# Metlino_MCH.net
KiCad netlist of a schematic drawn in Altium Designer
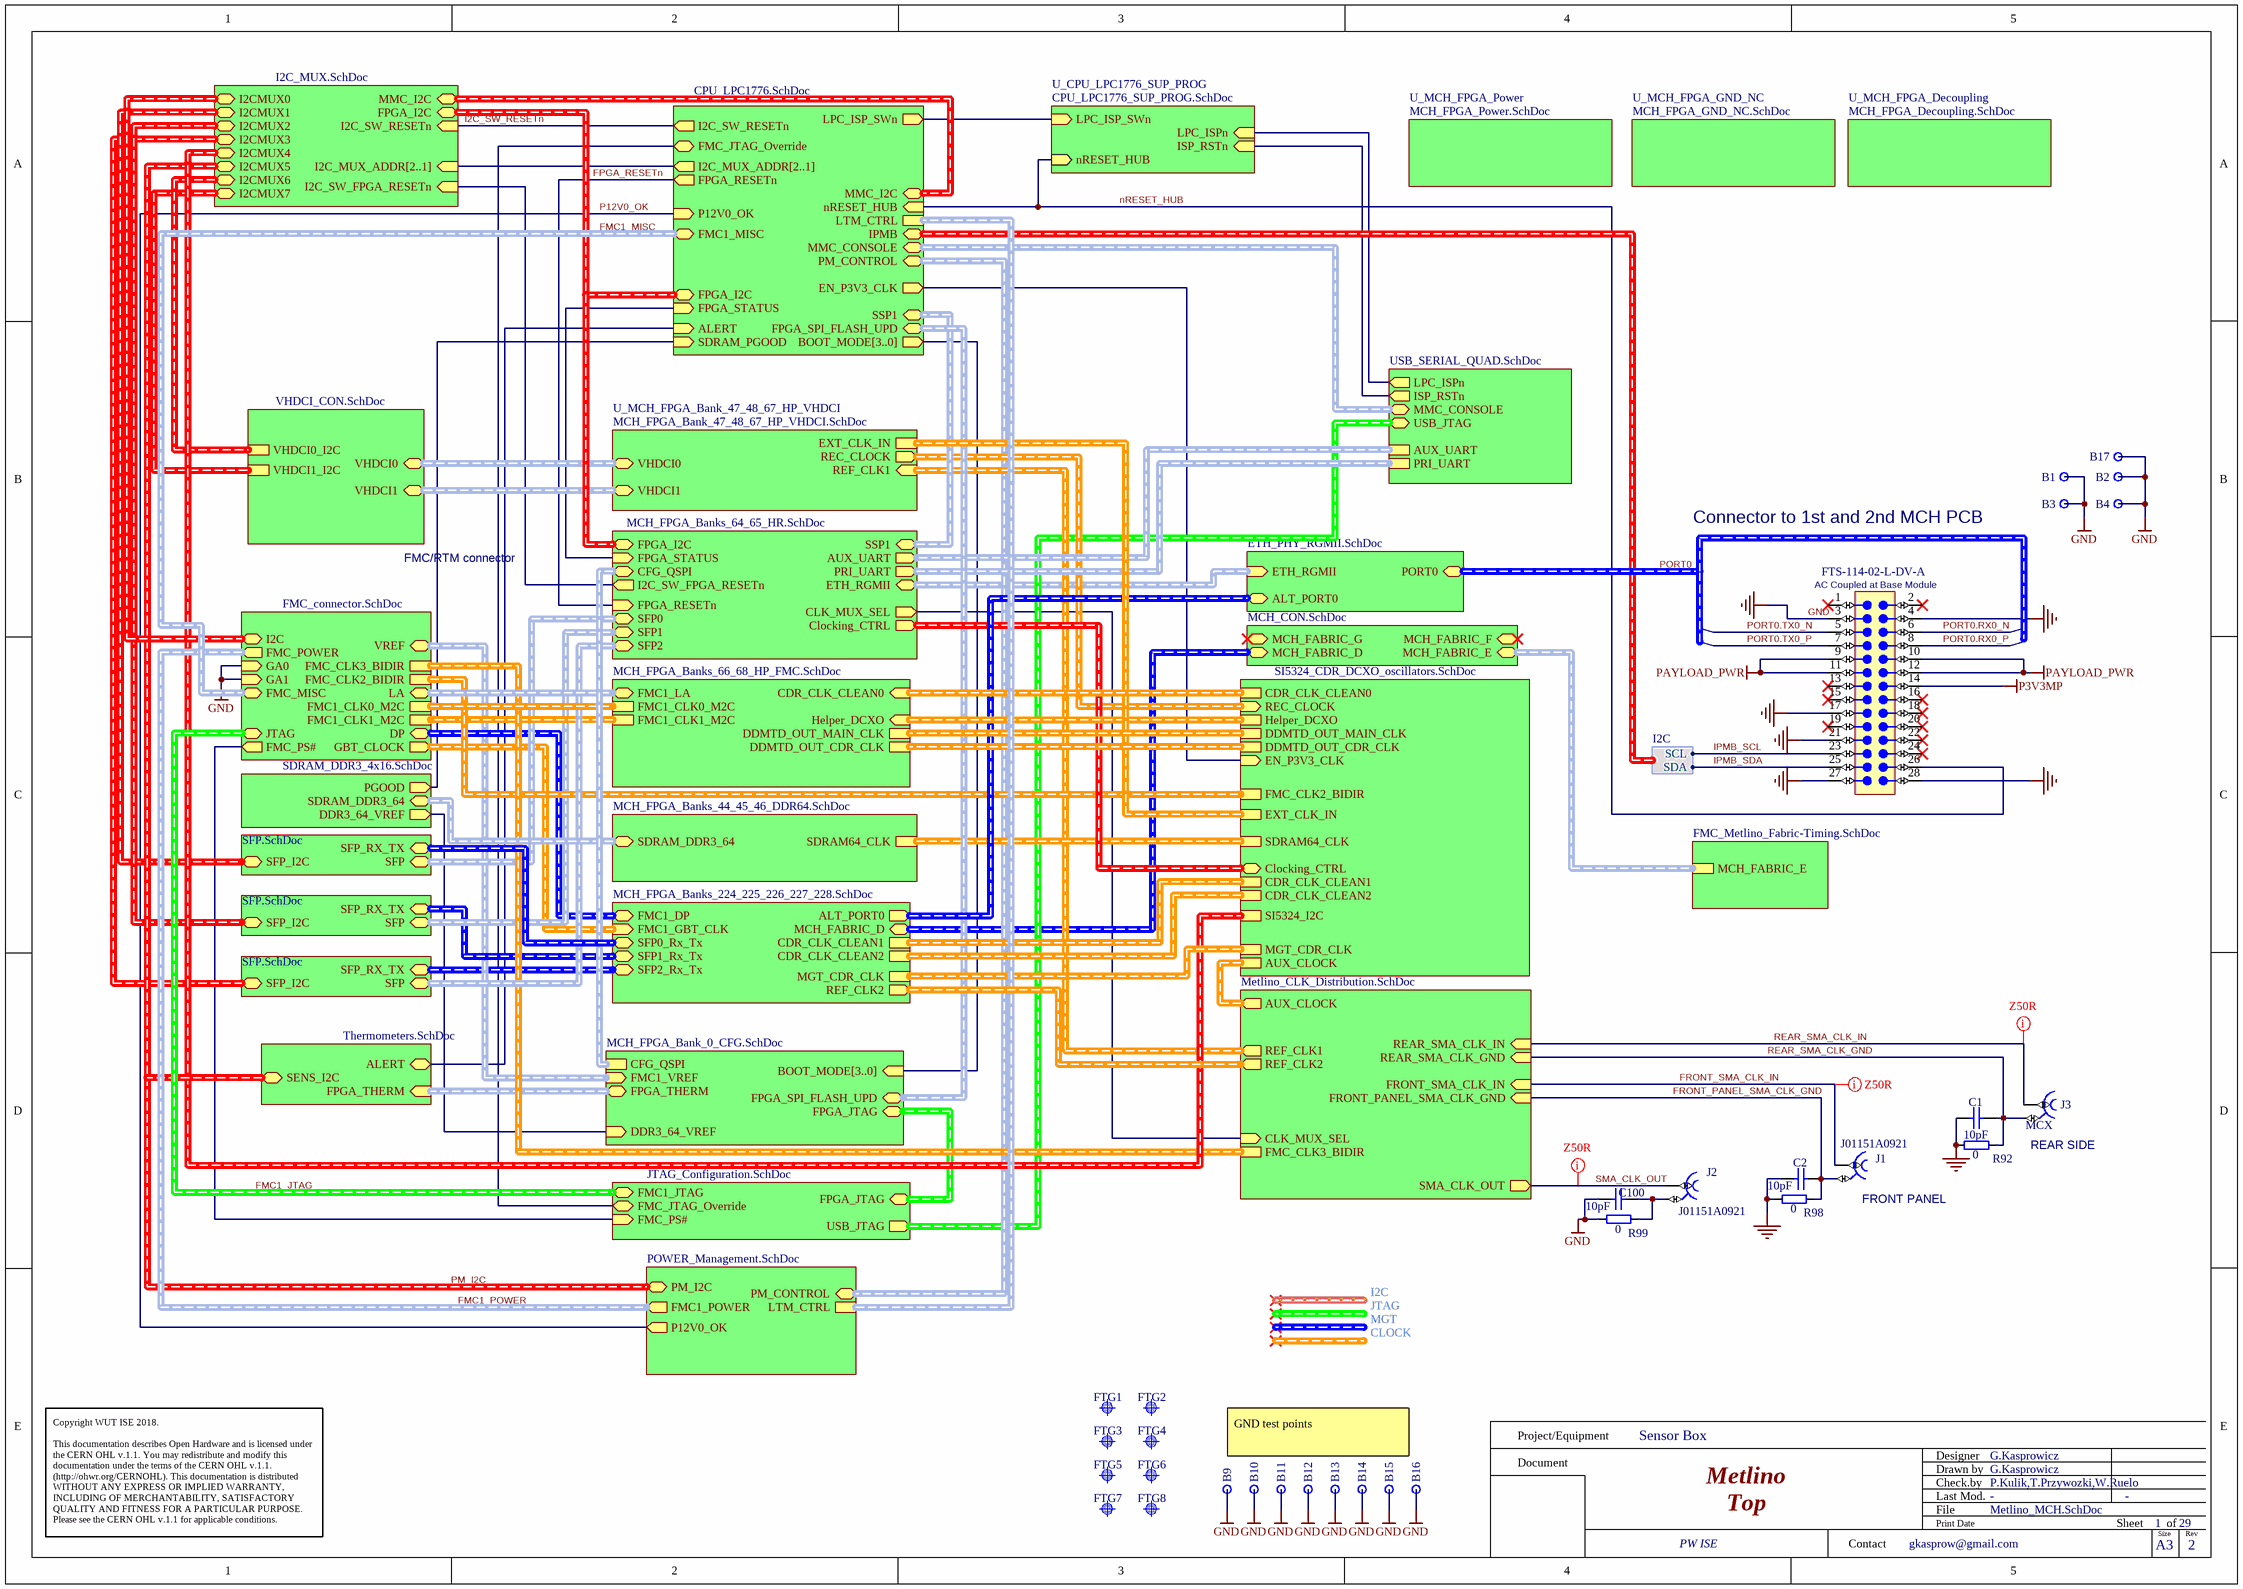
[diagram p0: Metlino_MCH.SchDoc]

(export (version "E")
  (design (tool "Eeschema 10.0.6"))
  (components
    (comp (ref "B1")
      (value "Plated Hole")
      (footprint "MTG320_550")
      (description "Single Terminal Socket")
      (fields (field (name "PART NUMBER") "PLATED_HOLE3.2_PAD5.5") (field (name "AUTHOR") "CERN DEM JMW"))
      (libsource (lib "Eletro-mechanical") (part "Single Terminal Socket"))
    )
    (comp (ref "B2")
      (value "Plated Hole")
      (footprint "MTG320_550")
      (description "Single Terminal Socket")
      (fields (field (name "PART NUMBER") "PLATED_HOLE3.2_PAD5.5") (field (name "AUTHOR") "CERN DEM JMW"))
      (libsource (lib "Eletro-mechanical") (part "Single Terminal Socket"))
    )
    (comp (ref "B3")
      (value "Plated Hole")
      (footprint "MTG320_550")
      (description "Single Terminal Socket")
      (fields (field (name "PART NUMBER") "PLATED_HOLE3.2_PAD5.5") (field (name "AUTHOR") "CERN DEM JMW"))
      (libsource (lib "Eletro-mechanical") (part "Single Terminal Socket"))
    )
    (comp (ref "B4")
      (value "Plated Hole")
      (footprint "MTG320_550")
      (description "Single Terminal Socket")
      (fields (field (name "PART NUMBER") "PLATED_HOLE3.2_PAD5.5") (field (name "AUTHOR") "CERN DEM JMW"))
      (libsource (lib "Eletro-mechanical") (part "Single Terminal Socket"))
    )
    (comp (ref "B9")
      (value "Plated Hole")
      (footprint "c130h80")
      (description "Single Terminal Socket")
      (fields (field (name "PART NUMBER") "PLATED_HOLE0.8_PAD1.3") (field (name "AUTHOR") "CERN DEM JLC"))
      (libsource (lib "Eletro-mechanical") (part "Single Terminal Socket"))
    )
    (comp (ref "B10")
      (value "Plated Hole")
      (footprint "c130h80")
      (description "Single Terminal Socket")
      (fields (field (name "PART NUMBER") "PLATED_HOLE0.8_PAD1.3") (field (name "AUTHOR") "CERN DEM JLC"))
      (libsource (lib "Eletro-mechanical") (part "Single Terminal Socket"))
    )
    (comp (ref "B11")
      (value "Plated Hole")
      (footprint "c130h80")
      (description "Single Terminal Socket")
      (fields (field (name "PART NUMBER") "PLATED_HOLE0.8_PAD1.3") (field (name "AUTHOR") "CERN DEM JLC"))
      (libsource (lib "Eletro-mechanical") (part "Single Terminal Socket"))
    )
    (comp (ref "B12")
      (value "Plated Hole")
      (footprint "c130h80")
      (description "Single Terminal Socket")
      (fields (field (name "PART NUMBER") "PLATED_HOLE0.8_PAD1.3") (field (name "AUTHOR") "CERN DEM JLC"))
      (libsource (lib "Eletro-mechanical") (part "Single Terminal Socket"))
    )
    (comp (ref "B13")
      (value "Plated Hole")
      (footprint "c130h80")
      (description "Single Terminal Socket")
      (fields (field (name "PART NUMBER") "PLATED_HOLE0.8_PAD1.3") (field (name "AUTHOR") "CERN DEM JLC"))
      (libsource (lib "Eletro-mechanical") (part "Single Terminal Socket"))
    )
    (comp (ref "B14")
      (value "Plated Hole")
      (footprint "c130h80")
      (description "Single Terminal Socket")
      (fields (field (name "PART NUMBER") "PLATED_HOLE0.8_PAD1.3") (field (name "AUTHOR") "CERN DEM JLC"))
      (libsource (lib "Eletro-mechanical") (part "Single Terminal Socket"))
    )
    (comp (ref "B15")
      (value "Plated Hole")
      (footprint "c130h80")
      (description "Single Terminal Socket")
      (fields (field (name "PART NUMBER") "PLATED_HOLE0.8_PAD1.3") (field (name "AUTHOR") "CERN DEM JLC"))
      (libsource (lib "Eletro-mechanical") (part "Single Terminal Socket"))
    )
    (comp (ref "B16")
      (value "Plated Hole")
      (footprint "c130h80")
      (description "Single Terminal Socket")
      (fields (field (name "PART NUMBER") "PLATED_HOLE0.8_PAD1.3") (field (name "AUTHOR") "CERN DEM JLC"))
      (libsource (lib "Eletro-mechanical") (part "Single Terminal Socket"))
    )
    (comp (ref "B17")
      (value "Plated Hole")
      (footprint "MTG320_550")
      (description "Single Terminal Socket")
      (fields (field (name "PART NUMBER") "PLATED_HOLE3.2_PAD5.5") (field (name "AUTHOR") "CERN DEM JMW"))
      (libsource (lib "Eletro-mechanical") (part "Single Terminal Socket"))
    )
    (comp (ref "C1")
      (value "10pF")
      (footprint "CAPC1608X87N")
      (description "Non-polarised capacitor")
      (fields
        (field (name "MANUFACTURER PART NUMBER") "CC0603_10PF_50V_5%_NP0")
        (field (name "MANUFACTURER") "GENERIC")
        (field (name "AUTHOR") "CERN DEM JLC")
      )
      (libsource (lib "Capacitors") (part "Capacitor - non polarized"))
    )
    (comp (ref "C2")
      (value "10pF")
      (footprint "CAPC1608X87N")
      (description "Non-polarised capacitor")
      (fields
        (field (name "MANUFACTURER PART NUMBER") "CC0603_10PF_50V_5%_NP0")
        (field (name "MANUFACTURER") "GENERIC")
        (field (name "AUTHOR") "CERN DEM JLC")
      )
      (libsource (lib "Capacitors") (part "Capacitor - non polarized"))
    )
    (comp (ref "C100")
      (value "10pF")
      (footprint "CAPC1608X87N")
      (description "Non-polarised capacitor")
      (fields
        (field (name "MANUFACTURER PART NUMBER") "CC0603_10PF_50V_5%_NP0")
        (field (name "MANUFACTURER") "GENERIC")
        (field (name "AUTHOR") "CERN DEM JLC")
      )
      (libsource (lib "Capacitors") (part "Capacitor - non polarized"))
    )
    (comp (ref "FTG1")
      (value "Use only in PCB")
      (footprint "FIDUCIAL_TOP_C100-200")
      (description "Fiducial Target")
      (fields (field (name "PART NUMBER") "FIDUCIAL_TARGET_C100-200") (field (name "AUTHOR") "CERN DEM JLC"))
      (libsource (lib "Eletro-mechanical") (part "Fiducial Target"))
    )
    (comp (ref "FTG2")
      (value "Use only in PCB")
      (footprint "FIDUCIAL_TOP_S100-200")
      (description "Fiducial Target")
      (fields (field (name "PART NUMBER") "FIDUCIAL_TARGET_S100-200") (field (name "AUTHOR") "CERN DEM JLC"))
      (libsource (lib "Eletro-mechanical") (part "Fiducial Target"))
    )
    (comp (ref "FTG3")
      (value "Use only in PCB")
      (footprint "FIDUCIAL_TOP_C100-200")
      (description "Fiducial Target")
      (fields (field (name "PART NUMBER") "FIDUCIAL_TARGET_C100-200") (field (name "AUTHOR") "CERN DEM JLC"))
      (libsource (lib "Eletro-mechanical") (part "Fiducial Target"))
    )
    (comp (ref "FTG4")
      (value "Use only in PCB")
      (footprint "FIDUCIAL_TOP_S100-200")
      (description "Fiducial Target")
      (fields (field (name "PART NUMBER") "FIDUCIAL_TARGET_S100-200") (field (name "AUTHOR") "CERN DEM JLC"))
      (libsource (lib "Eletro-mechanical") (part "Fiducial Target"))
    )
    (comp (ref "FTG5")
      (value "Use only in PCB")
      (footprint "FIDUCIAL_TOP_C100-200")
      (description "Fiducial Target")
      (fields (field (name "PART NUMBER") "FIDUCIAL_TARGET_C100-200") (field (name "AUTHOR") "CERN DEM JLC"))
      (libsource (lib "Eletro-mechanical") (part "Fiducial Target"))
    )
    (comp (ref "FTG6")
      (value "Use only in PCB")
      (footprint "FIDUCIAL_TOP_S100-200")
      (description "Fiducial Target")
      (fields (field (name "PART NUMBER") "FIDUCIAL_TARGET_S100-200") (field (name "AUTHOR") "CERN DEM JLC"))
      (libsource (lib "Eletro-mechanical") (part "Fiducial Target"))
    )
    (comp (ref "FTG7")
      (value "Use only in PCB")
      (footprint "FIDUCIAL_TOP_C100-200")
      (description "Fiducial Target")
      (fields (field (name "PART NUMBER") "FIDUCIAL_TARGET_C100-200") (field (name "AUTHOR") "CERN DEM JLC"))
      (libsource (lib "Eletro-mechanical") (part "Fiducial Target"))
    )
    (comp (ref "FTG8")
      (value "Use only in PCB")
      (footprint "FIDUCIAL_TOP_S100-200")
      (description "Fiducial Target")
      (fields (field (name "PART NUMBER") "FIDUCIAL_TARGET_S100-200") (field (name "AUTHOR") "CERN DEM JLC"))
      (libsource (lib "Eletro-mechanical") (part "Fiducial Target"))
    )
    (comp (ref "J1")
      (value "SMA")
      (footprint "TELEGARTNER_J01151A0921")
      (fields
        (field (name "MANUFACTURER PART NUMBER") "J01151A0921")
        (field (name "MANUFACTURER") "TELEGARTNER")
        (field (name "PART NUMBER") "TELEGARTNER_J01151A0921")
        (field (name "AUTHOR") "CERN DEM JLC")
      )
      (libsource (lib "Connectors") (part "Coax_1Female_1Shield"))
    )
    (comp (ref "J2")
      (value "SMA")
      (footprint "TELEGARTNER_J01151A0921")
      (fields
        (field (name "MANUFACTURER PART NUMBER") "J01151A0921")
        (field (name "MANUFACTURER") "TELEGARTNER")
        (field (name "PART NUMBER") "TELEGARTNER_J01151A0921")
        (field (name "AUTHOR") "CERN DEM JLC")
      )
      (libsource (lib "Connectors") (part "Coax_1Female_1Shield"))
    )
    (comp (ref "J3")
      (value "MCX")
      (footprint "AMPHENOL_ARF2521-ND")
      (fields
        (field (name "PART NUMBER") "AMPHENOL_ARF2521-ND")
        (field (name "MANUFACTURER") "AMPHENOL")
        (field (name "AUTHOR") "GK")
      )
      (libsource (lib "LIBRARY_SCH") (part "CON_MCX"))
    )
    (comp (ref "J4")
      (value "Header 28")
      (footprint "SAMTEC_FTS-114-02-L-DV-A")
      (description "Connector 28 Male")
      (fields
        (field (name "MANUFACTURER PART NUMBER") "FTS-114-02-L-DV-A")
        (field (name "MANUFACTURER") "SAMTEC")
        (field (name "PART NUMBER") "SAMTEC_FTS-114-02-L-DV-A")
        (field (name "AUTHOR") "CERN DEM MR")
      )
      (libsource (lib "Connectors") (part "Connector 28 Male"))
    )
    (comp (ref "R92")
      (value "0")
      (footprint "RESC1608X55N")
      (description "Resistor")
      (fields
        (field (name "MANUFACTURER PART NUMBER") "R0603_0R_JUMPER")
        (field (name "MANUFACTURER") "GENERIC")
        (field (name "AUTHOR") "CERN DEM JLC")
      )
      (libsource (lib "Resistors") (part "Resistor"))
    )
    (comp (ref "R98")
      (value "0")
      (footprint "RESC1608X55N")
      (description "Resistor")
      (fields
        (field (name "MANUFACTURER PART NUMBER") "R0603_0R_JUMPER")
        (field (name "MANUFACTURER") "GENERIC")
        (field (name "AUTHOR") "CERN DEM JLC")
      )
      (libsource (lib "Resistors") (part "Resistor"))
    )
    (comp (ref "R99")
      (value "0")
      (footprint "RESC1608X55N")
      (description "Resistor")
      (fields
        (field (name "MANUFACTURER PART NUMBER") "R0603_0R_JUMPER")
        (field (name "MANUFACTURER") "GENERIC")
        (field (name "AUTHOR") "CERN DEM JLC")
      )
      (libsource (lib "Resistors") (part "Resistor"))
    )
  )
  (nets
    (net (code "39") (name "/FRONT_PANEL_SMA_CLK_GND") (class "Default")
      (node (ref "C2") (pin "1") (pinfunction "1_1") (pintype "passive"))
      (node (ref "J1") (pin "2") (pinfunction "2_2") (pintype "bidirectional"))
      (node (ref "R98") (pin "2") (pinfunction "2_2") (pintype "passive"))
    )
    (net (code "40") (name "/FRONT_SMA_CLK_IN") (class "Default")
      (node (ref "J1") (pin "1") (pinfunction "1_1") (pintype "bidirectional"))
    )
    (net (code "53") (name "/IPMB_SCL") (class "Default")
      (node (ref "J4") (pin "23") (pinfunction "23_23") (pintype "bidirectional"))
    )
    (net (code "54") (name "/IPMB_SDA") (class "Default")
      (node (ref "J4") (pin "25") (pinfunction "25_25") (pintype "bidirectional"))
    )
    (net (code "69") (name "/PORT0.RX0_N") (class "Default")
      (node (ref "J4") (pin "6") (pinfunction "6_6") (pintype "bidirectional"))
    )
    (net (code "70") (name "/PORT0.RX0_P") (class "Default")
      (node (ref "J4") (pin "8") (pinfunction "8_8") (pintype "bidirectional"))
    )
    (net (code "71") (name "/PORT0.TX0_N") (class "Default")
      (node (ref "J4") (pin "5") (pinfunction "5_5") (pintype "bidirectional"))
    )
    (net (code "72") (name "/PORT0.TX0_P") (class "Default")
      (node (ref "J4") (pin "7") (pinfunction "7_7") (pintype "bidirectional"))
    )
    (net (code "74") (name "/REAR_SMA_CLK_GND") (class "Default")
      (node (ref "C1") (pin "1") (pinfunction "1_1") (pintype "passive"))
      (node (ref "J3") (pin "2") (pinfunction "2_2") (pintype "bidirectional"))
      (node (ref "R92") (pin "2") (pinfunction "2_2") (pintype "passive"))
    )
    (net (code "75") (name "/REAR_SMA_CLK_IN") (class "Default")
      (node (ref "J3") (pin "1") (pinfunction "1_1") (pintype "bidirectional"))
    )
    (net (code "87") (name "/SMA_CLK_OUT") (class "Default")
      (node (ref "J2") (pin "1") (pinfunction "1_1") (pintype "bidirectional"))
    )
    (net (code "92") (name "/nRESET_HUB") (class "Default")
      (node (ref "J4") (pin "26") (pinfunction "26_26") (pintype "bidirectional"))
    )
    (net (code "99") (name "GND") (class "Default")
      (node (ref "B1") (pin "1") (pinfunction "1_1") (pintype "bidirectional"))
      (node (ref "B10") (pin "1") (pinfunction "1_1") (pintype "bidirectional"))
      (node (ref "B11") (pin "1") (pinfunction "1_1") (pintype "bidirectional"))
      (node (ref "B12") (pin "1") (pinfunction "1_1") (pintype "bidirectional"))
      (node (ref "B13") (pin "1") (pinfunction "1_1") (pintype "bidirectional"))
      (node (ref "B14") (pin "1") (pinfunction "1_1") (pintype "bidirectional"))
      (node (ref "B15") (pin "1") (pinfunction "1_1") (pintype "bidirectional"))
      (node (ref "B16") (pin "1") (pinfunction "1_1") (pintype "bidirectional"))
      (node (ref "B17") (pin "1") (pinfunction "1_1") (pintype "bidirectional"))
      (node (ref "B2") (pin "1") (pinfunction "1_1") (pintype "bidirectional"))
      (node (ref "B3") (pin "1") (pinfunction "1_1") (pintype "bidirectional"))
      (node (ref "B4") (pin "1") (pinfunction "1_1") (pintype "bidirectional"))
      (node (ref "B9") (pin "1") (pinfunction "1_1") (pintype "bidirectional"))
      (node (ref "C1") (pin "2") (pinfunction "2_2") (pintype "passive"))
      (node (ref "C100") (pin "2") (pinfunction "2_2") (pintype "passive"))
      (node (ref "C2") (pin "2") (pinfunction "2_2") (pintype "passive"))
      (node (ref "J4") (pin "17") (pinfunction "17_17") (pintype "bidirectional"))
      (node (ref "J4") (pin "21") (pinfunction "21_21") (pintype "bidirectional"))
      (node (ref "J4") (pin "27") (pinfunction "27_27") (pintype "bidirectional"))
      (node (ref "J4") (pin "28") (pinfunction "28_28") (pintype "bidirectional"))
      (node (ref "J4") (pin "3") (pinfunction "3_3") (pintype "bidirectional"))
      (node (ref "J4") (pin "4") (pinfunction "4_4") (pintype "bidirectional"))
      (node (ref "R92") (pin "1") (pinfunction "1_1") (pintype "passive"))
      (node (ref "R98") (pin "1") (pinfunction "1_1") (pintype "passive"))
      (node (ref "R99") (pin "1") (pinfunction "1_1") (pintype "passive"))
    )
    (net (code "100") (name "Net-(C100-Pad1)") (class "Default")
      (node (ref "C100") (pin "1") (pinfunction "1_1") (pintype "passive"))
      (node (ref "J2") (pin "2") (pinfunction "2_2") (pintype "bidirectional"))
      (node (ref "R99") (pin "2") (pinfunction "2_2") (pintype "passive"))
    )
    (net (code "101") (name "P3V3MP") (class "Default")
      (node (ref "J4") (pin "14") (pinfunction "14_14") (pintype "bidirectional"))
    )
    (net (code "102") (name "PAYLOAD_PWR") (class "Default")
      (node (ref "J4") (pin "10") (pinfunction "10_10") (pintype "bidirectional"))
      (node (ref "J4") (pin "11") (pinfunction "11_11") (pintype "bidirectional"))
      (node (ref "J4") (pin "12") (pinfunction "12_12") (pintype "bidirectional"))
      (node (ref "J4") (pin "9") (pinfunction "9_9") (pintype "bidirectional"))
    )
    (net (code "103") (name "unconnected-(J4-Pad1)") (class "Default")
      (node (ref "J4") (pin "1") (pinfunction "1_1") (pintype "bidirectional+no_connect"))
    )
    (net (code "104") (name "unconnected-(J4-Pad2)") (class "Default")
      (node (ref "J4") (pin "2") (pinfunction "2_2") (pintype "bidirectional+no_connect"))
    )
    (net (code "105") (name "unconnected-(J4-Pad13)") (class "Default")
      (node (ref "J4") (pin "13") (pinfunction "13_13") (pintype "bidirectional+no_connect"))
    )
    (net (code "106") (name "unconnected-(J4-Pad15)") (class "Default")
      (node (ref "J4") (pin "15") (pinfunction "15_15") (pintype "bidirectional+no_connect"))
    )
    (net (code "107") (name "unconnected-(J4-Pad16)") (class "Default")
      (node (ref "J4") (pin "16") (pinfunction "16_16") (pintype "bidirectional+no_connect"))
    )
    (net (code "108") (name "unconnected-(J4-Pad18)") (class "Default")
      (node (ref "J4") (pin "18") (pinfunction "18_18") (pintype "bidirectional+no_connect"))
    )
    (net (code "109") (name "unconnected-(J4-Pad19)") (class "Default")
      (node (ref "J4") (pin "19") (pinfunction "19_19") (pintype "bidirectional+no_connect"))
    )
    (net (code "110") (name "unconnected-(J4-Pad20)") (class "Default")
      (node (ref "J4") (pin "20") (pinfunction "20_20") (pintype "bidirectional+no_connect"))
    )
    (net (code "111") (name "unconnected-(J4-Pad22)") (class "Default")
      (node (ref "J4") (pin "22") (pinfunction "22_22") (pintype "bidirectional+no_connect"))
    )
    (net (code "112") (name "unconnected-(J4-Pad24)") (class "Default")
      (node (ref "J4") (pin "24") (pinfunction "24_24") (pintype "bidirectional+no_connect"))
    )
  )
)
